# Nebulizer_medical.net
KiCad netlist of a schematic drawn in Altium Designer
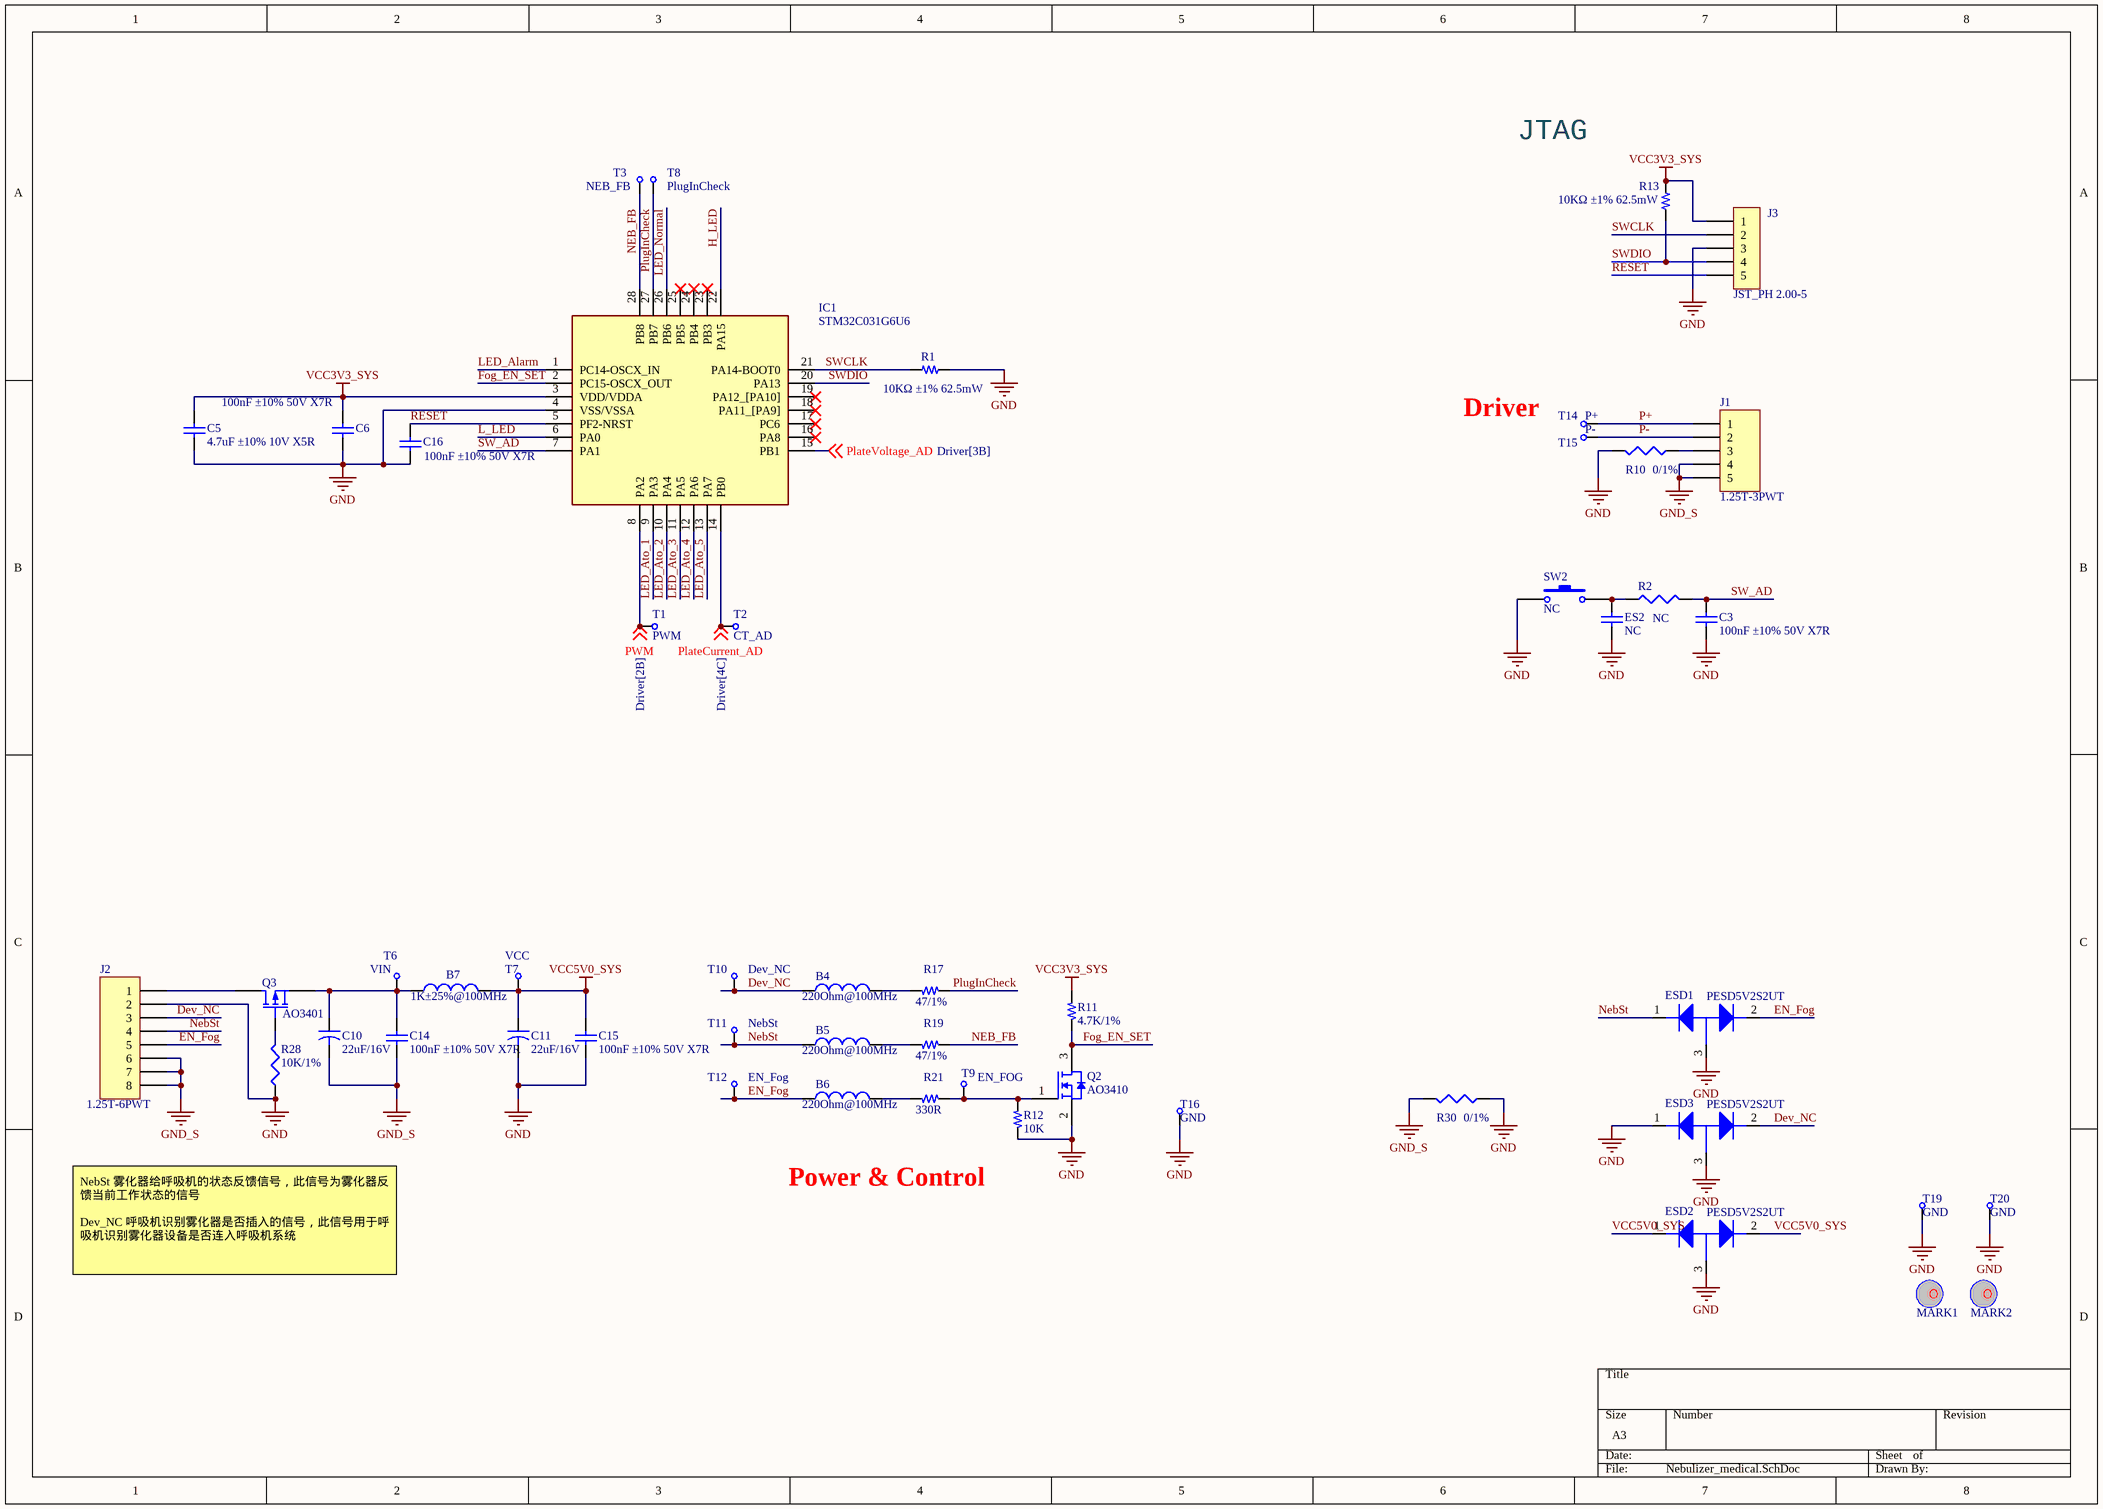
[diagram p0: Nebulizer_medical.SchDoc]

(export (version "E")
  (design (tool "Eeschema 10.0.6"))
  (components
    (comp (ref "B4")
      (value "220Ohm@100MHz")
      (footprint "0402-B")
      (description "Inductor")
      (fields (field (name "PUBLISHER") "Altium Limited"))
      (libsource (lib "Miscellaneous Devices") (part "Inductor"))
    )
    (comp (ref "B5")
      (value "220Ohm@100MHz")
      (footprint "0402-B")
      (description "Inductor")
      (fields (field (name "PUBLISHER") "Altium Limited"))
      (libsource (lib "Miscellaneous Devices") (part "Inductor"))
    )
    (comp (ref "B6")
      (value "220Ohm@100MHz")
      (footprint "0402-B")
      (description "Inductor")
      (fields (field (name "PUBLISHER") "Altium Limited"))
      (libsource (lib "Miscellaneous Devices") (part "Inductor"))
    )
    (comp (ref "B7")
      (value "1K±25%@100MHz")
      (footprint "0805-B")
      (description "Inductor")
      (fields (field (name "PUBLISHER") "Altium Limited"))
      (libsource (lib "Miscellaneous Devices") (part "Inductor"))
    )
    (comp (ref "C3")
      (value "100nF ±10% 50V X7R")
      (footprint "C0402")
      (description "Capacitor (Semiconductor SIM Model)")
      (fields (field (name "PUBLISHER") "Altium Limited"))
      (libsource (lib "Miscellaneous Devices") (part "Cap Semi"))
    )
    (comp (ref "C5")
      (value "4.7uF ±10% 10V X5R")
      (footprint "C0402")
      (description "CL05A475KP5NRNC")
      (fields (field (name "PUBLISHER") "Altium Limited"))
      (libsource (lib "Component") (part "Cap"))
    )
    (comp (ref "C6")
      (value "100nF ±10% 50V X7R")
      (footprint "C0402")
      (description "Capacitor")
      (fields (field (name "PUBLISHER") "Altium Limited"))
      (libsource (lib "Component") (part "Cap"))
    )
    (comp (ref "C10")
      (value "22uF/16V")
      (footprint "C0805")
      (description "Capacitor")
      (fields (field (name "PUBLISHER") "Altium Limited"))
      (libsource (lib "Miscellaneous Devices") (part "Cap2"))
    )
    (comp (ref "C11")
      (value "22uF/16V")
      (footprint "C0805")
      (description "Capacitor")
      (fields (field (name "PUBLISHER") "Altium Limited"))
      (libsource (lib "Miscellaneous Devices") (part "Cap2"))
    )
    (comp (ref "C14")
      (value "100nF ±10% 50V X7R")
      (footprint "C0402")
      (description "Capacitor (Semiconductor SIM Model)")
      (fields (field (name "PUBLISHER") "Altium Limited"))
      (libsource (lib "Miscellaneous Devices") (part "Cap Semi"))
    )
    (comp (ref "C15")
      (value "100nF ±10% 50V X7R")
      (footprint "C0402")
      (description "Capacitor (Semiconductor SIM Model)")
      (fields (field (name "PUBLISHER") "Altium Limited"))
      (libsource (lib "Miscellaneous Devices") (part "Cap Semi"))
    )
    (comp (ref "C16")
      (value "100nF ±10% 50V X7R")
      (footprint "C0402")
      (description "Capacitor")
      (fields (field (name "PUBLISHER") "Altium Limited"))
      (libsource (lib "Component") (part "Cap"))
    )
    (comp (ref "ES2")
      (value "NC")
      (footprint "C0402")
      (description "Capacitor (Semiconductor SIM Model)")
      (fields (field (name "PUBLISHER") "Altium Limited"))
      (libsource (lib "Miscellaneous Devices") (part "Cap Semi"))
    )
    (comp (ref "ESD1")
      (value "PESD5V2S2UT")
      (footprint "SOT23")
      (description "ESD")
      (libsource (lib "Atomizer_medical") (part "ESD"))
    )
    (comp (ref "ESD2")
      (value "PESD5V2S2UT")
      (footprint "SOT23")
      (description "ESD")
      (libsource (lib "Atomizer_medical") (part "ESD"))
    )
    (comp (ref "ESD3")
      (value "PESD5V2S2UT")
      (footprint "SOT23")
      (description "ESD")
      (libsource (lib "Atomizer_medical") (part "ESD"))
    )
    (comp (ref "IC1")
      (value "STM32C031G6U6")
      (footprint "QFN50P400X400X60-28N-D")
      (description "Integrated Circuit")
      (fields (field (name "MOUSER PART NUMBER") "511-STM32C031G6U6"))
      (libsource (lib "SamacSys") (part "STM32C031G6U6"))
    )
    (comp (ref "J1")
      (value "1.25T-3PWT")
      (footprint "WAFER_1.25MMX3P_180")
      (description "Header, 5-Pin")
      (fields (field (name "PUBLISHER") "Altium Limited"))
      (libsource (lib "Miscellaneous Connectors") (part "Header 5"))
    )
    (comp (ref "J2")
      (value "1.25T-6PWT")
      (footprint "WAFER_1.25MMX6P_180")
      (description "Header, 8-Pin")
      (fields (field (name "PUBLISHER") "Altium Limited"))
      (libsource (lib "Miscellaneous Connectors") (part "Header 8"))
    )
    (comp (ref "J3")
      (value "JST_PH 2.00-5")
      (footprint "JST_PH 2.00-5")
      (description "品牌：JST 型号：B5B-PH-K-S，直插，间距2.00，5pin")
      (libsource (lib "connectors") (part "JST_PH 2.00-5"))
    )
    (comp (ref "MARK1")
      (value "MARK_POINT")
      (footprint "MARK_POINT")
      (libsource (lib "others") (part "MARK_POINT"))
    )
    (comp (ref "MARK2")
      (value "MARK_POINT")
      (footprint "MARK_POINT")
      (libsource (lib "others") (part "MARK_POINT"))
    )
    (comp (ref "Q2")
      (value "AO3410")
      (footprint "SOT23-3")
      (description "AOS,AO3410,SOT23-3,-55~+150°C,")
      (libsource (lib "IC") (part "AO3410"))
    )
    (comp (ref "Q3")
      (value "AO3401")
      (footprint "SOT23")
      (description "P-Channel MOSFET")
      (fields (field (name "PUBLISHER") "Altium Limited"))
      (libsource (lib "Miscellaneous Devices") (part "MOSFET-P"))
    )
    (comp (ref "R1") (value "10KΩ ±1% 62.5mW") (footprint "R0402") (libsource (lib "Device") (part "R-0603")))
    (comp (ref "R2")
      (value "NC")
      (footprint "R0402")
      (description "Resistor")
      (fields (field (name "PUBLISHER") "Altium Limited"))
      (libsource (lib "Miscellaneous Devices") (part "Res3"))
    )
    (comp (ref "R10")
      (value "0/1%")
      (footprint "R0603")
      (description "Resistor")
      (fields (field (name "PUBLISHER") "Altium Limited"))
      (libsource (lib "Miscellaneous Devices") (part "Res3"))
    )
    (comp (ref "R11") (value "4.7K/1%") (footprint "R0402") (libsource (lib "Device") (part "R-0603")))
    (comp (ref "R12") (value "10K") (footprint "R0402") (libsource (lib "Device") (part "R-0603")))
    (comp (ref "R13")
      (value "10KΩ ±1% 62.5mW")
      (footprint "R0402")
      (libsource (lib "Device") (part "R-0603"))
    )
    (comp (ref "R17") (value "47/1%") (footprint "R0402") (libsource (lib "Device") (part "R-0603")))
    (comp (ref "R19") (value "47/1%") (footprint "R0402") (libsource (lib "Device") (part "R-0603")))
    (comp (ref "R21") (value "330R") (footprint "R0402") (libsource (lib "Device") (part "R-0603")))
    (comp (ref "R28")
      (value "10K/1%")
      (footprint "R0402")
      (description "Resistor")
      (fields (field (name "PUBLISHER") "Altium Limited"))
      (libsource (lib "Miscellaneous Devices") (part "Res3"))
    )
    (comp (ref "R30")
      (value "0/1%")
      (footprint "R0603")
      (description "Resistor")
      (fields (field (name "PUBLISHER") "Altium Limited"))
      (libsource (lib "Miscellaneous Devices") (part "Res3"))
    )
    (comp (ref "SW2")
      (value "NC")
      (footprint "HTS-52MB")
      (description "Switch")
      (fields (field (name "PUBLISHER") "Altium Limited"))
      (libsource (lib "Miscellaneous Devices") (part "SW-PB"))
    )
    (comp (ref "T1")
      (value "PWM")
      (footprint "TP-SIP-1-Small1")
      (libsource (lib "others") (part "TP-SIP-1-Small"))
    )
    (comp (ref "T2")
      (value "CT_AD")
      (footprint "TP-SIP-1-Small1")
      (libsource (lib "others") (part "TP-SIP-1-Small"))
    )
    (comp (ref "T3")
      (value "NEB_FB")
      (footprint "TP-SIP-1-Small1")
      (libsource (lib "others") (part "TP-SIP-1-Small"))
    )
    (comp (ref "T6")
      (value "VIN")
      (footprint "TP-SIP-1-Small1")
      (libsource (lib "others") (part "TP-SIP-1-Small"))
    )
    (comp (ref "T7")
      (value "VCC")
      (footprint "TP-SIP-1-Small1")
      (libsource (lib "others") (part "TP-SIP-1-Small"))
    )
    (comp (ref "T8")
      (value "PlugInCheck")
      (footprint "TP-SIP-1-Small1")
      (libsource (lib "others") (part "TP-SIP-1-Small"))
    )
    (comp (ref "T9")
      (value "EN_FOG")
      (footprint "TP-SIP-1-Small1")
      (libsource (lib "others") (part "TP-SIP-1-Small"))
    )
    (comp (ref "T10")
      (value "Dev_NC")
      (footprint "TP-SIP-1-Small1")
      (libsource (lib "others") (part "TP-SIP-1-Small"))
    )
    (comp (ref "T11")
      (value "NebSt")
      (footprint "TP-SIP-1-Small1")
      (libsource (lib "others") (part "TP-SIP-1-Small"))
    )
    (comp (ref "T12")
      (value "EN_Fog")
      (footprint "TP-SIP-1-Small1")
      (libsource (lib "others") (part "TP-SIP-1-Small"))
    )
    (comp (ref "T14")
      (value "P+")
      (footprint "TP-SIP-1-Small1")
      (libsource (lib "others") (part "TP-SIP-1-Small"))
    )
    (comp (ref "T15")
      (value "P-")
      (footprint "TP-SIP-1-Small1")
      (libsource (lib "others") (part "TP-SIP-1-Small"))
    )
    (comp (ref "T16")
      (value "GND")
      (footprint "TP-SIP-1-Small1")
      (libsource (lib "others") (part "TP-SIP-1-Small"))
    )
    (comp (ref "T19")
      (value "GND")
      (footprint "TP-SIP-1-Small1")
      (libsource (lib "others") (part "TP-SIP-1-Small"))
    )
    (comp (ref "T20")
      (value "GND")
      (footprint "TP-SIP-1-Small1")
      (libsource (lib "others") (part "TP-SIP-1-Small"))
    )
  )
  (nets
    (net (code "1") (name "/Dev_NC") (class "Default")
      (node (ref "B4") (pin "1") (pinfunction "1_1") (pintype "passive"))
      (node (ref "ESD3") (pin "2") (pinfunction "S_2") (pintype "passive"))
      (node (ref "J2") (pin "3") (pinfunction "3_3") (pintype "passive"))
      (node (ref "T10") (pin "1") (pinfunction "1_1") (pintype "passive"))
    )
    (net (code "2") (name "/EN_Fog") (class "Default")
      (node (ref "B6") (pin "1") (pinfunction "1_1") (pintype "passive"))
      (node (ref "ESD1") (pin "2") (pinfunction "S_2") (pintype "passive"))
      (node (ref "J2") (pin "5") (pinfunction "5_5") (pintype "passive"))
      (node (ref "T12") (pin "1") (pinfunction "1_1") (pintype "passive"))
    )
    (net (code "3") (name "/Fog_EN_SET") (class "Default")
      (node (ref "IC1") (pin "2") (pinfunction "PC15-OSCX_OUT_2") (pintype "passive"))
      (node (ref "Q2") (pin "3") (pinfunction "D_3") (pintype "passive"))
      (node (ref "R11") (pin "2") (pinfunction "2_2") (pintype "passive"))
    )
    (net (code "4") (name "/H_LED") (class "Default")
      (node (ref "IC1") (pin "22") (pinfunction "PA15_22") (pintype "passive"))
    )
    (net (code "5") (name "/LED_Alarm") (class "Default")
      (node (ref "IC1") (pin "1") (pinfunction "PC14-OSCX_IN_1") (pintype "passive"))
    )
    (net (code "6") (name "/LED_Ato_1") (class "Default")
      (node (ref "IC1") (pin "9") (pinfunction "PA3_9") (pintype "passive"))
    )
    (net (code "7") (name "/LED_Ato_2") (class "Default")
      (node (ref "IC1") (pin "10") (pinfunction "PA4_10") (pintype "passive"))
    )
    (net (code "8") (name "/LED_Ato_3") (class "Default")
      (node (ref "IC1") (pin "11") (pinfunction "PA5_11") (pintype "passive"))
    )
    (net (code "9") (name "/LED_Ato_4") (class "Default")
      (node (ref "IC1") (pin "12") (pinfunction "PA6_12") (pintype "passive"))
    )
    (net (code "10") (name "/LED_Ato_5") (class "Default")
      (node (ref "IC1") (pin "13") (pinfunction "PA7_13") (pintype "passive"))
    )
    (net (code "11") (name "/LED_Normal") (class "Default")
      (node (ref "IC1") (pin "26") (pinfunction "PB6_26") (pintype "passive"))
    )
    (net (code "12") (name "/L_LED") (class "Default")
      (node (ref "IC1") (pin "6") (pinfunction "PA0_6") (pintype "passive"))
    )
    (net (code "13") (name "/NEB_FB") (class "Default")
      (node (ref "IC1") (pin "28") (pinfunction "PB8_28") (pintype "passive"))
      (node (ref "R19") (pin "1") (pinfunction "1_1") (pintype "passive"))
      (node (ref "T3") (pin "1") (pinfunction "1_1") (pintype "passive"))
    )
    (net (code "14") (name "/NebSt") (class "Default")
      (node (ref "B5") (pin "1") (pinfunction "1_1") (pintype "passive"))
      (node (ref "ESD1") (pin "1") (pinfunction "S_1") (pintype "passive"))
      (node (ref "J2") (pin "4") (pinfunction "4_4") (pintype "passive"))
      (node (ref "T11") (pin "1") (pinfunction "1_1") (pintype "passive"))
    )
    (net (code "15") (name "/P+") (class "Default")
      (node (ref "J1") (pin "1") (pinfunction "1_1") (pintype "passive"))
      (node (ref "T14") (pin "1") (pinfunction "1_1") (pintype "passive"))
    )
    (net (code "16") (name "/P-") (class "Default")
      (node (ref "J1") (pin "2") (pinfunction "2_2") (pintype "passive"))
      (node (ref "T15") (pin "1") (pinfunction "1_1") (pintype "passive"))
    )
    (net (code "17") (name "/PlugInCheck") (class "Default")
      (node (ref "IC1") (pin "27") (pinfunction "PB7_27") (pintype "passive"))
      (node (ref "R17") (pin "1") (pinfunction "1_1") (pintype "passive"))
      (node (ref "T8") (pin "1") (pinfunction "1_1") (pintype "passive"))
    )
    (net (code "18") (name "/RESET") (class "Default")
      (node (ref "C16") (pin "2") (pinfunction "2_2") (pintype "passive"))
      (node (ref "IC1") (pin "5") (pinfunction "PF2-NRST_5") (pintype "passive"))
      (node (ref "J3") (pin "5") (pinfunction "5_5") (pintype "passive"))
    )
    (net (code "19") (name "/SWCLK") (class "Default")
      (node (ref "IC1") (pin "21") (pinfunction "PA14-BOOT0_21") (pintype "passive"))
      (node (ref "J3") (pin "2") (pinfunction "2_2") (pintype "passive"))
      (node (ref "R1") (pin "2") (pinfunction "2_2") (pintype "passive"))
    )
    (net (code "20") (name "/SWDIO") (class "Default")
      (node (ref "IC1") (pin "20") (pinfunction "PA13_20") (pintype "passive"))
      (node (ref "J3") (pin "4") (pinfunction "4_4") (pintype "passive"))
      (node (ref "R13") (pin "1") (pinfunction "1_1") (pintype "passive"))
    )
    (net (code "21") (name "/SW_AD") (class "Default")
      (node (ref "C3") (pin "2") (pinfunction "2_2") (pintype "passive"))
      (node (ref "IC1") (pin "7") (pinfunction "PA1_7") (pintype "passive"))
      (node (ref "R2") (pin "2") (pinfunction "2_2") (pintype "passive"))
    )
    (net (code "22") (name "GND") (class "Default")
      (node (ref "C11") (pin "2") (pinfunction "2_2") (pintype "passive"))
      (node (ref "C15") (pin "2") (pinfunction "2_2") (pintype "passive"))
      (node (ref "C16") (pin "1") (pinfunction "1_1") (pintype "passive"))
      (node (ref "C3") (pin "1") (pinfunction "1_1") (pintype "passive"))
      (node (ref "C5") (pin "1") (pinfunction "1_1") (pintype "passive"))
      (node (ref "C6") (pin "1") (pinfunction "1_1") (pintype "passive"))
      (node (ref "ES2") (pin "2") (pinfunction "2_2") (pintype "passive"))
      (node (ref "ESD1") (pin "3") (pinfunction "G_3") (pintype "passive"))
      (node (ref "ESD2") (pin "3") (pinfunction "G_3") (pintype "passive"))
      (node (ref "ESD3") (pin "1") (pinfunction "S_1") (pintype "passive"))
      (node (ref "ESD3") (pin "3") (pinfunction "G_3") (pintype "passive"))
      (node (ref "IC1") (pin "4") (pinfunction "VSS/VSSA_4") (pintype "passive"))
      (node (ref "J2") (pin "2") (pinfunction "2_2") (pintype "passive"))
      (node (ref "J3") (pin "3") (pinfunction "3_3") (pintype "passive"))
      (node (ref "Q2") (pin "2") (pinfunction "S_2") (pintype "passive"))
      (node (ref "R1") (pin "1") (pinfunction "1_1") (pintype "passive"))
      (node (ref "R10") (pin "2") (pinfunction "2_2") (pintype "passive"))
      (node (ref "R12") (pin "2") (pinfunction "2_2") (pintype "passive"))
      (node (ref "R28") (pin "1") (pinfunction "1_1") (pintype "passive"))
      (node (ref "R30") (pin "1") (pinfunction "1_1") (pintype "passive"))
      (node (ref "SW2") (pin "1") (pinfunction "1_1") (pintype "passive"))
      (node (ref "T16") (pin "1") (pinfunction "1_1") (pintype "passive"))
      (node (ref "T19") (pin "1") (pinfunction "1_1") (pintype "passive"))
      (node (ref "T20") (pin "1") (pinfunction "1_1") (pintype "passive"))
    )
    (net (code "23") (name "GND_S") (class "Default")
      (node (ref "C10") (pin "2") (pinfunction "2_2") (pintype "passive"))
      (node (ref "C14") (pin "2") (pinfunction "2_2") (pintype "passive"))
      (node (ref "J1") (pin "4") (pinfunction "4_4") (pintype "passive"))
      (node (ref "J1") (pin "5") (pinfunction "5_5") (pintype "passive"))
      (node (ref "J2") (pin "6") (pinfunction "6_6") (pintype "passive"))
      (node (ref "J2") (pin "7") (pinfunction "7_7") (pintype "passive"))
      (node (ref "J2") (pin "8") (pinfunction "8_8") (pintype "passive"))
      (node (ref "R30") (pin "2") (pinfunction "2_2") (pintype "passive"))
    )
    (net (code "24") (name "Net-(B4-Pad2)") (class "Default")
      (node (ref "B4") (pin "2") (pinfunction "2_2") (pintype "passive"))
      (node (ref "R17") (pin "2") (pinfunction "2_2") (pintype "passive"))
    )
    (net (code "25") (name "Net-(B5-Pad2)") (class "Default")
      (node (ref "B5") (pin "2") (pinfunction "2_2") (pintype "passive"))
      (node (ref "R19") (pin "2") (pinfunction "2_2") (pintype "passive"))
    )
    (net (code "26") (name "Net-(B6-Pad2)") (class "Default")
      (node (ref "B6") (pin "2") (pinfunction "2_2") (pintype "passive"))
      (node (ref "R21") (pin "2") (pinfunction "2_2") (pintype "passive"))
    )
    (net (code "27") (name "Net-(ES2-Pad1)") (class "Default")
      (node (ref "ES2") (pin "1") (pinfunction "1_1") (pintype "passive"))
      (node (ref "R2") (pin "1") (pinfunction "1_1") (pintype "passive"))
      (node (ref "SW2") (pin "2") (pinfunction "2_2") (pintype "passive"))
    )
    (net (code "28") (name "Net-(J1-Pad3)") (class "Default")
      (node (ref "J1") (pin "3") (pinfunction "3_3") (pintype "passive"))
      (node (ref "R10") (pin "1") (pinfunction "1_1") (pintype "passive"))
    )
    (net (code "29") (name "Net-(Q2-G)") (class "Default")
      (node (ref "Q2") (pin "1") (pinfunction "G_1") (pintype "passive"))
      (node (ref "R12") (pin "1") (pinfunction "1_1") (pintype "passive"))
      (node (ref "R21") (pin "1") (pinfunction "1_1") (pintype "passive"))
      (node (ref "T9") (pin "1") (pinfunction "1_1") (pintype "passive"))
    )
    (net (code "30") (name "Net-(Q3-D)") (class "Default")
      (node (ref "J2") (pin "1") (pinfunction "1_1") (pintype "passive"))
      (node (ref "Q3") (pin "2") (pinfunction "D_2") (pintype "passive"))
    )
    (net (code "31") (name "Net-(Q3-G)") (class "Default")
      (node (ref "Q3") (pin "1") (pinfunction "G_1") (pintype "passive"))
      (node (ref "R28") (pin "2") (pinfunction "2_2") (pintype "passive"))
    )
    (net (code "32") (name "Net-(Q3-S)") (class "Default")
      (node (ref "B7") (pin "1") (pinfunction "1_1") (pintype "passive"))
      (node (ref "C10") (pin "1") (pinfunction "1_1") (pintype "passive"))
      (node (ref "C14") (pin "1") (pinfunction "1_1") (pintype "passive"))
      (node (ref "Q3") (pin "3") (pinfunction "S_3") (pintype "passive"))
      (node (ref "T6") (pin "1") (pinfunction "1_1") (pintype "passive"))
    )
    (net (code "33") (name "PWM") (class "Default")
      (node (ref "IC1") (pin "8") (pinfunction "PA2_8") (pintype "passive"))
      (node (ref "T1") (pin "1") (pinfunction "1_1") (pintype "passive"))
    )
    (net (code "34") (name "PlateCurrent_AD") (class "Default")
      (node (ref "IC1") (pin "14") (pinfunction "PB0_14") (pintype "passive"))
      (node (ref "T2") (pin "1") (pinfunction "1_1") (pintype "passive"))
    )
    (net (code "35") (name "PlateVoltage_AD") (class "Default")
      (node (ref "IC1") (pin "15") (pinfunction "PB1_15") (pintype "passive"))
    )
    (net (code "36") (name "VCC3V3_SYS") (class "Default")
      (node (ref "C5") (pin "2") (pinfunction "2_2") (pintype "passive"))
      (node (ref "C6") (pin "2") (pinfunction "2_2") (pintype "passive"))
      (node (ref "IC1") (pin "3") (pinfunction "VDD/VDDA_3") (pintype "passive"))
      (node (ref "J3") (pin "1") (pinfunction "1_1") (pintype "passive"))
      (node (ref "R11") (pin "1") (pinfunction "1_1") (pintype "passive"))
      (node (ref "R13") (pin "2") (pinfunction "2_2") (pintype "passive"))
    )
    (net (code "37") (name "VCC5V0_SYS") (class "Default")
      (node (ref "B7") (pin "2") (pinfunction "2_2") (pintype "passive"))
      (node (ref "C11") (pin "1") (pinfunction "1_1") (pintype "passive"))
      (node (ref "C15") (pin "1") (pinfunction "1_1") (pintype "passive"))
      (node (ref "ESD2") (pin "1") (pinfunction "S_1") (pintype "passive"))
      (node (ref "ESD2") (pin "2") (pinfunction "S_2") (pintype "passive"))
      (node (ref "T7") (pin "1") (pinfunction "1_1") (pintype "passive"))
    )
    (net (code "38") (name "unconnected-(IC1-PA8-Pad16)") (class "Default")
      (node (ref "IC1") (pin "16") (pinfunction "PA8_16") (pintype "passive+no_connect"))
    )
    (net (code "39") (name "unconnected-(IC1-PA11_[PA9]-Pad18)") (class "Default")
      (node (ref "IC1") (pin "18") (pinfunction "PA11_[PA9]_18") (pintype "passive+no_connect"))
    )
    (net (code "40") (name "unconnected-(IC1-PA12_[PA10]-Pad19)") (class "Default")
      (node (ref "IC1") (pin "19") (pinfunction "PA12_[PA10]_19") (pintype "passive+no_connect"))
    )
    (net (code "41") (name "unconnected-(IC1-PB3-Pad23)") (class "Default")
      (node (ref "IC1") (pin "23") (pinfunction "PB3_23") (pintype "passive+no_connect"))
    )
    (net (code "42") (name "unconnected-(IC1-PB4-Pad24)") (class "Default")
      (node (ref "IC1") (pin "24") (pinfunction "PB4_24") (pintype "passive+no_connect"))
    )
    (net (code "43") (name "unconnected-(IC1-PB5-Pad25)") (class "Default")
      (node (ref "IC1") (pin "25") (pinfunction "PB5_25") (pintype "passive+no_connect"))
    )
    (net (code "44") (name "unconnected-(IC1-PC6-Pad17)") (class "Default")
      (node (ref "IC1") (pin "17") (pinfunction "PC6_17") (pintype "passive+no_connect"))
    )
  )
)
